# Panel.net
KiCad netlist of a schematic drawn in Altium Designer
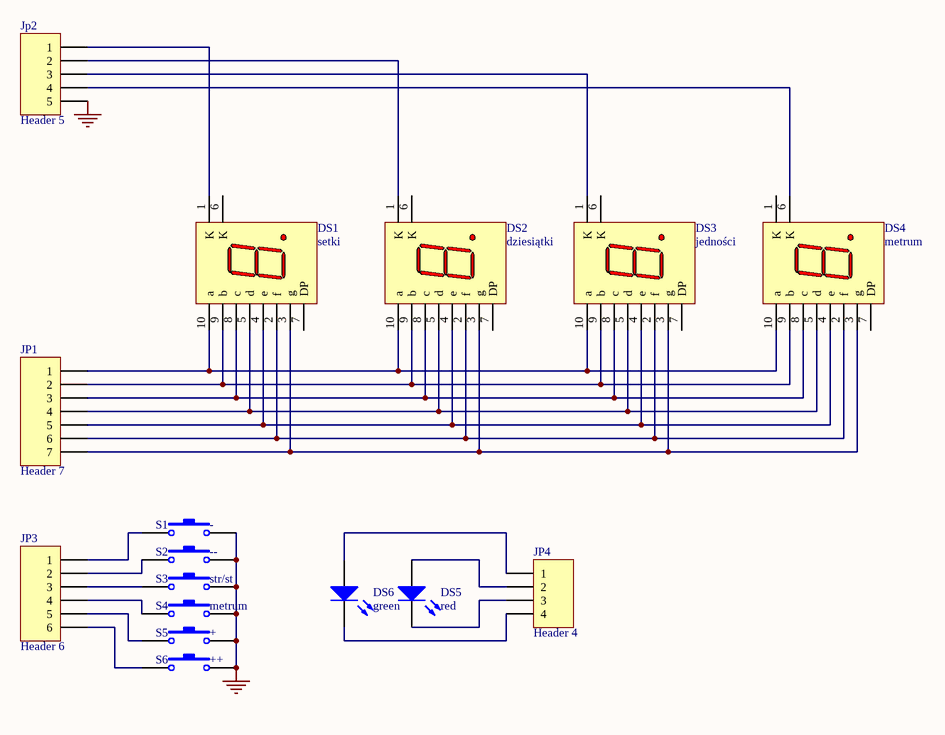
[diagram p0: Panel.SchDoc]

(export (version "E")
  (design (tool "Eeschema 10.0.6"))
  (components
    (comp (ref "DS1")
      (value "setki")
      (footprint "LEDDIP-10/C5.08")
      (description "7.6 mm Black Surface 7-Segment Display: CC, RH DP")
      (fields (field (name "PUBLISHER") "Altium Limited"))
      (libsource (lib "Miscellaneous Devices") (part "Dpy Red-CC"))
    )
    (comp (ref "DS2")
      (value "dziesiątki")
      (footprint "LEDDIP-10/C5.08")
      (description "7.6 mm Black Surface 7-Segment Display: CC, RH DP")
      (fields (field (name "PUBLISHER") "Altium Limited"))
      (libsource (lib "Miscellaneous Devices") (part "Dpy Red-CC"))
    )
    (comp (ref "DS3")
      (value "jedności")
      (footprint "LEDDIP-10/C5.08")
      (description "7.6 mm Black Surface 7-Segment Display: CC, RH DP")
      (fields (field (name "PUBLISHER") "Altium Limited"))
      (libsource (lib "Miscellaneous Devices") (part "Dpy Red-CC"))
    )
    (comp (ref "DS4")
      (value "metrum")
      (footprint "LEDDIP-10/C5.08")
      (description "7.6 mm Black Surface 7-Segment Display: CC, RH DP")
      (fields (field (name "PUBLISHER") "Altium Limited"))
      (libsource (lib "Miscellaneous Devices") (part "Dpy Red-CC"))
    )
    (comp (ref "DS5")
      (value "red")
      (footprint "LED-1")
      (description "Typical RED GaAs LED")
      (fields (field (name "PUBLISHER") "Altium Limited"))
      (libsource (lib "Miscellaneous Devices") (part "LED1"))
    )
    (comp (ref "DS6")
      (value "green")
      (footprint "LED-1")
      (description "Typical RED GaAs LED")
      (fields (field (name "PUBLISHER") "Altium Limited"))
      (libsource (lib "Miscellaneous Devices") (part "LED1"))
    )
    (comp (ref "JP1")
      (value "Header 7")
      (footprint "HDR1X7")
      (description "Header, 7-Pin")
      (fields (field (name "PUBLISHER") "Altium Limited"))
      (libsource (lib "Miscellaneous Connectors") (part "Header 7"))
    )
    (comp (ref "Jp2")
      (value "Header 5")
      (footprint "HDR1X5")
      (description "Header, 5-Pin")
      (fields (field (name "PUBLISHER") "Altium Limited"))
      (libsource (lib "Miscellaneous Connectors") (part "Header 5"))
    )
    (comp (ref "JP3")
      (value "Header 6")
      (footprint "HDR1X6")
      (description "Header, 6-Pin")
      (fields (field (name "PUBLISHER") "Altium Limited"))
      (libsource (lib "Miscellaneous Connectors") (part "Header 6"))
    )
    (comp (ref "JP4")
      (value "Header 4")
      (footprint "HDR1X4")
      (description "Header, 4-Pin")
      (fields (field (name "PUBLISHER") "Altium Limited"))
      (libsource (lib "Miscellaneous Connectors") (part "Header 4"))
    )
    (comp (ref "S1")
      (value "-")
      (footprint "SPST-2")
      (description "Switch")
      (fields (field (name "PUBLISHER") "Altium Limited"))
      (libsource (lib "Miscellaneous Devices") (part "SW-PB"))
    )
    (comp (ref "S2")
      (value "--")
      (footprint "SPST-2")
      (description "Switch")
      (fields (field (name "PUBLISHER") "Altium Limited"))
      (libsource (lib "Miscellaneous Devices") (part "SW-PB"))
    )
    (comp (ref "S3")
      (value "str/st")
      (footprint "SPST-2")
      (description "Switch")
      (fields (field (name "PUBLISHER") "Altium Limited"))
      (libsource (lib "Miscellaneous Devices") (part "SW-PB"))
    )
    (comp (ref "S4")
      (value "metrum")
      (footprint "SPST-2")
      (description "Switch")
      (fields (field (name "PUBLISHER") "Altium Limited"))
      (libsource (lib "Miscellaneous Devices") (part "SW-PB"))
    )
    (comp (ref "S5")
      (value "+")
      (footprint "SPST-2")
      (description "Switch")
      (fields (field (name "PUBLISHER") "Altium Limited"))
      (libsource (lib "Miscellaneous Devices") (part "SW-PB"))
    )
    (comp (ref "S6")
      (value "++")
      (footprint "SPST-2")
      (description "Switch")
      (fields (field (name "PUBLISHER") "Altium Limited"))
      (libsource (lib "Miscellaneous Devices") (part "SW-PB"))
    )
  )
  (nets
    (net (code "1") (name "GND") (class "Default")
      (node (ref "Jp2") (pin "5") (pinfunction "5_5") (pintype "passive"))
      (node (ref "S1") (pin "2") (pinfunction "2_2") (pintype "passive"))
      (node (ref "S2") (pin "2") (pinfunction "2_2") (pintype "passive"))
      (node (ref "S3") (pin "2") (pinfunction "2_2") (pintype "passive"))
      (node (ref "S4") (pin "2") (pinfunction "2_2") (pintype "passive"))
      (node (ref "S5") (pin "2") (pinfunction "2_2") (pintype "passive"))
      (node (ref "S6") (pin "2") (pinfunction "2_2") (pintype "passive"))
    )
    (net (code "2") (name "Net-(DS1-K-Pad1)") (class "Default")
      (node (ref "DS1") (pin "1") (pinfunction "K_1") (pintype "passive"))
      (node (ref "Jp2") (pin "1") (pinfunction "1_1") (pintype "passive"))
    )
    (net (code "3") (name "Net-(DS1-a)") (class "Default")
      (node (ref "DS1") (pin "10") (pinfunction "a_10") (pintype "passive"))
      (node (ref "DS2") (pin "10") (pinfunction "a_10") (pintype "passive"))
      (node (ref "DS3") (pin "10") (pinfunction "a_10") (pintype "passive"))
      (node (ref "DS4") (pin "10") (pinfunction "a_10") (pintype "passive"))
      (node (ref "JP1") (pin "1") (pinfunction "1_1") (pintype "passive"))
    )
    (net (code "4") (name "Net-(DS1-b)") (class "Default")
      (node (ref "DS1") (pin "9") (pinfunction "b_9") (pintype "passive"))
      (node (ref "DS2") (pin "9") (pinfunction "b_9") (pintype "passive"))
      (node (ref "DS3") (pin "9") (pinfunction "b_9") (pintype "passive"))
      (node (ref "DS4") (pin "9") (pinfunction "b_9") (pintype "passive"))
      (node (ref "JP1") (pin "2") (pinfunction "2_2") (pintype "passive"))
    )
    (net (code "5") (name "Net-(DS1-c)") (class "Default")
      (node (ref "DS1") (pin "8") (pinfunction "c_8") (pintype "passive"))
      (node (ref "DS2") (pin "8") (pinfunction "c_8") (pintype "passive"))
      (node (ref "DS3") (pin "8") (pinfunction "c_8") (pintype "passive"))
      (node (ref "DS4") (pin "8") (pinfunction "c_8") (pintype "passive"))
      (node (ref "JP1") (pin "3") (pinfunction "3_3") (pintype "passive"))
    )
    (net (code "6") (name "Net-(DS1-d)") (class "Default")
      (node (ref "DS1") (pin "5") (pinfunction "d_5") (pintype "passive"))
      (node (ref "DS2") (pin "5") (pinfunction "d_5") (pintype "passive"))
      (node (ref "DS3") (pin "5") (pinfunction "d_5") (pintype "passive"))
      (node (ref "DS4") (pin "5") (pinfunction "d_5") (pintype "passive"))
      (node (ref "JP1") (pin "4") (pinfunction "4_4") (pintype "passive"))
    )
    (net (code "7") (name "Net-(DS1-e)") (class "Default")
      (node (ref "DS1") (pin "4") (pinfunction "e_4") (pintype "passive"))
      (node (ref "DS2") (pin "4") (pinfunction "e_4") (pintype "passive"))
      (node (ref "DS3") (pin "4") (pinfunction "e_4") (pintype "passive"))
      (node (ref "DS4") (pin "4") (pinfunction "e_4") (pintype "passive"))
      (node (ref "JP1") (pin "5") (pinfunction "5_5") (pintype "passive"))
    )
    (net (code "8") (name "Net-(DS1-f)") (class "Default")
      (node (ref "DS1") (pin "2") (pinfunction "f_2") (pintype "passive"))
      (node (ref "DS2") (pin "2") (pinfunction "f_2") (pintype "passive"))
      (node (ref "DS3") (pin "2") (pinfunction "f_2") (pintype "passive"))
      (node (ref "DS4") (pin "2") (pinfunction "f_2") (pintype "passive"))
      (node (ref "JP1") (pin "6") (pinfunction "6_6") (pintype "passive"))
    )
    (net (code "9") (name "Net-(DS1-g)") (class "Default")
      (node (ref "DS1") (pin "3") (pinfunction "g_3") (pintype "passive"))
      (node (ref "DS2") (pin "3") (pinfunction "g_3") (pintype "passive"))
      (node (ref "DS3") (pin "3") (pinfunction "g_3") (pintype "passive"))
      (node (ref "DS4") (pin "3") (pinfunction "g_3") (pintype "passive"))
      (node (ref "JP1") (pin "7") (pinfunction "7_7") (pintype "passive"))
    )
    (net (code "10") (name "Net-(DS2-K-Pad1)") (class "Default")
      (node (ref "DS2") (pin "1") (pinfunction "K_1") (pintype "passive"))
      (node (ref "Jp2") (pin "2") (pinfunction "2_2") (pintype "passive"))
    )
    (net (code "11") (name "Net-(DS3-K-Pad1)") (class "Default")
      (node (ref "DS3") (pin "1") (pinfunction "K_1") (pintype "passive"))
      (node (ref "Jp2") (pin "3") (pinfunction "3_3") (pintype "passive"))
    )
    (net (code "12") (name "Net-(DS4-K-Pad6)") (class "Default")
      (node (ref "DS4") (pin "6") (pinfunction "K_6") (pintype "passive"))
      (node (ref "Jp2") (pin "4") (pinfunction "4_4") (pintype "passive"))
    )
    (net (code "13") (name "Net-(DS5-A)") (class "Default")
      (node (ref "DS5") (pin "1") (pinfunction "A_1") (pintype "passive"))
      (node (ref "JP4") (pin "2") (pinfunction "2_2") (pintype "passive"))
    )
    (net (code "14") (name "Net-(DS5-K)") (class "Default")
      (node (ref "DS5") (pin "2") (pinfunction "K_2") (pintype "passive"))
      (node (ref "JP4") (pin "3") (pinfunction "3_3") (pintype "passive"))
    )
    (net (code "15") (name "Net-(DS6-A)") (class "Default")
      (node (ref "DS6") (pin "1") (pinfunction "A_1") (pintype "passive"))
      (node (ref "JP4") (pin "1") (pinfunction "1_1") (pintype "passive"))
    )
    (net (code "16") (name "Net-(DS6-K)") (class "Default")
      (node (ref "DS6") (pin "2") (pinfunction "K_2") (pintype "passive"))
      (node (ref "JP4") (pin "4") (pinfunction "4_4") (pintype "passive"))
    )
    (net (code "17") (name "Net-(JP3-Pad1)") (class "Default")
      (node (ref "JP3") (pin "1") (pinfunction "1_1") (pintype "passive"))
      (node (ref "S1") (pin "1") (pinfunction "1_1") (pintype "passive"))
    )
    (net (code "18") (name "Net-(JP3-Pad2)") (class "Default")
      (node (ref "JP3") (pin "2") (pinfunction "2_2") (pintype "passive"))
      (node (ref "S2") (pin "1") (pinfunction "1_1") (pintype "passive"))
    )
    (net (code "19") (name "Net-(JP3-Pad3)") (class "Default")
      (node (ref "JP3") (pin "3") (pinfunction "3_3") (pintype "passive"))
      (node (ref "S3") (pin "1") (pinfunction "1_1") (pintype "passive"))
    )
    (net (code "20") (name "Net-(JP3-Pad4)") (class "Default")
      (node (ref "JP3") (pin "4") (pinfunction "4_4") (pintype "passive"))
      (node (ref "S4") (pin "1") (pinfunction "1_1") (pintype "passive"))
    )
    (net (code "21") (name "Net-(JP3-Pad5)") (class "Default")
      (node (ref "JP3") (pin "5") (pinfunction "5_5") (pintype "passive"))
      (node (ref "S5") (pin "1") (pinfunction "1_1") (pintype "passive"))
    )
    (net (code "22") (name "Net-(JP3-Pad6)") (class "Default")
      (node (ref "JP3") (pin "6") (pinfunction "6_6") (pintype "passive"))
      (node (ref "S6") (pin "1") (pinfunction "1_1") (pintype "passive"))
    )
    (net (code "23") (name "unconnected-(DS1-DP-Pad7)") (class "Default")
      (node (ref "DS1") (pin "7") (pinfunction "DP_7") (pintype "passive"))
    )
    (net (code "24") (name "unconnected-(DS1-K-Pad6)") (class "Default")
      (node (ref "DS1") (pin "6") (pinfunction "K_6") (pintype "passive"))
    )
    (net (code "25") (name "unconnected-(DS2-DP-Pad7)") (class "Default")
      (node (ref "DS2") (pin "7") (pinfunction "DP_7") (pintype "passive"))
    )
    (net (code "26") (name "unconnected-(DS2-K-Pad6)") (class "Default")
      (node (ref "DS2") (pin "6") (pinfunction "K_6") (pintype "passive"))
    )
    (net (code "27") (name "unconnected-(DS3-DP-Pad7)") (class "Default")
      (node (ref "DS3") (pin "7") (pinfunction "DP_7") (pintype "passive"))
    )
    (net (code "28") (name "unconnected-(DS3-K-Pad6)") (class "Default")
      (node (ref "DS3") (pin "6") (pinfunction "K_6") (pintype "passive"))
    )
    (net (code "29") (name "unconnected-(DS4-DP-Pad7)") (class "Default")
      (node (ref "DS4") (pin "7") (pinfunction "DP_7") (pintype "passive"))
    )
    (net (code "30") (name "unconnected-(DS4-K-Pad1)") (class "Default")
      (node (ref "DS4") (pin "1") (pinfunction "K_1") (pintype "passive"))
    )
  )
)
